# MCU.net
KiCad netlist of a schematic drawn in Altium Designer
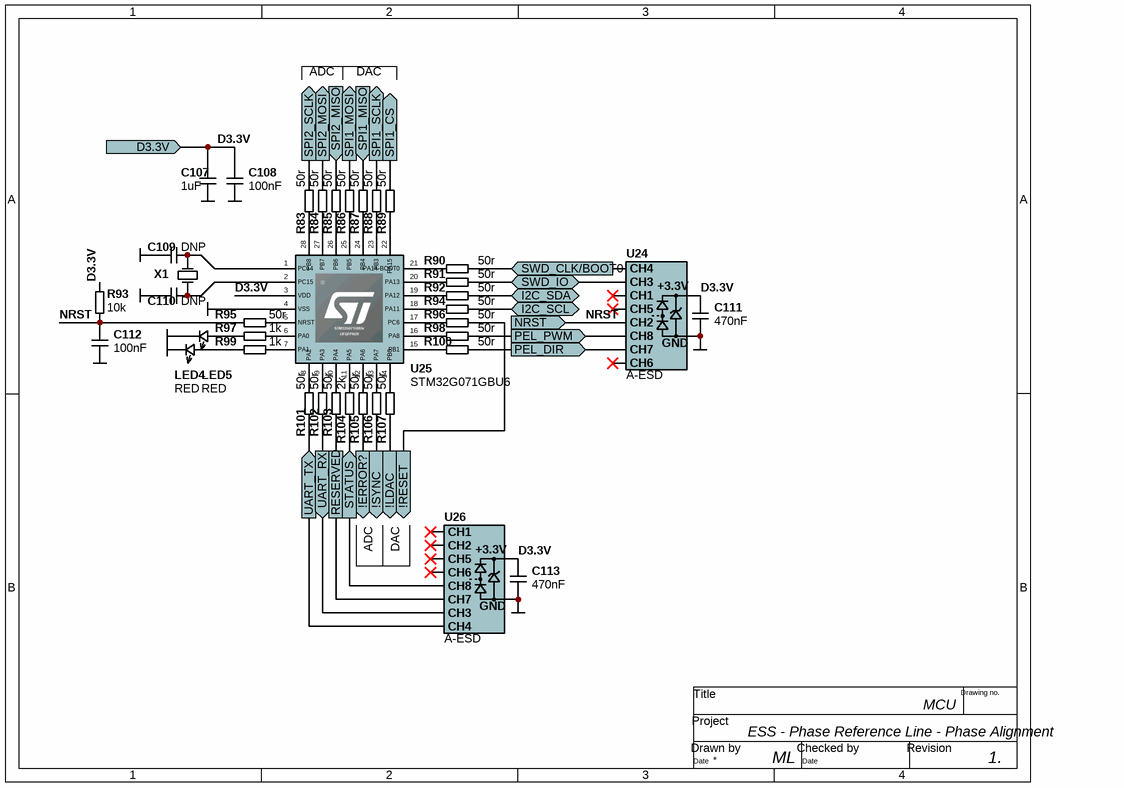
[diagram p0: MCU.SchDoc]

(export (version "E")
  (design (tool "Eeschema 10.0.6"))
  (components
    (comp (ref "C107")
      (value "1uF")
      (footprint "0805-Capacitor")
      (description "Capacitor 0805")
      (fields (field (name "TOLERANCE") "±20%"))
      (libsource (lib "PRL_PDC") (part "C_0805"))
    )
    (comp (ref "C108")
      (value "100nF")
      (footprint "0402-Capacitor")
      (description "Capacitor 0402")
      (fields (field (name "TOLERANCE") "±20%"))
      (libsource (lib "PRL_PDC") (part "C_0402"))
    )
    (comp (ref "C109")
      (value "DNP")
      (footprint "0402-Capacitor")
      (description "Capacitor 0402")
      (fields (field (name "TOLERANCE") "±20%"))
      (libsource (lib "PRL_PDC") (part "C_0402"))
    )
    (comp (ref "C110")
      (value "DNP")
      (footprint "0402-Capacitor")
      (description "Capacitor 0402")
      (fields (field (name "TOLERANCE") "±20%"))
      (libsource (lib "PRL_PDC") (part "C_0402"))
    )
    (comp (ref "C111")
      (value "470nF")
      (footprint "0402-Capacitor")
      (description "Capacitor 0402")
      (fields (field (name "TOLERANCE") "±20%"))
      (libsource (lib "PRL_PDC") (part "C_0402"))
    )
    (comp (ref "C112")
      (value "100nF")
      (footprint "0402-Capacitor")
      (description "Capacitor 0402")
      (fields (field (name "TOLERANCE") "±20%"))
      (libsource (lib "PRL_PDC") (part "C_0402"))
    )
    (comp (ref "C113")
      (value "470nF")
      (footprint "0402-Capacitor")
      (description "Capacitor 0402")
      (fields (field (name "TOLERANCE") "±20%"))
      (libsource (lib "PRL_PDC") (part "C_0402"))
    )
    (comp (ref "LED4") (value "RED") (footprint "LED0603") (libsource (lib "PRL_PDC") (part "LED0603")))
    (comp (ref "LED5") (value "RED") (footprint "LED0603") (libsource (lib "PRL_PDC") (part "LED0603")))
    (comp (ref "R83")
      (value "50r")
      (footprint "0402-RESISTOR")
      (description "Resistor 0402")
      (fields (field (name "TOLERANCE") "±1%"))
      (libsource (lib "PRL_PDC") (part "R_0402"))
    )
    (comp (ref "R84")
      (value "50r")
      (footprint "0402-RESISTOR")
      (description "Resistor 0402")
      (fields (field (name "TOLERANCE") "±1%"))
      (libsource (lib "PRL_PDC") (part "R_0402"))
    )
    (comp (ref "R85")
      (value "50r")
      (footprint "0402-RESISTOR")
      (description "Resistor 0402")
      (fields (field (name "TOLERANCE") "±1%"))
      (libsource (lib "PRL_PDC") (part "R_0402"))
    )
    (comp (ref "R86")
      (value "50r")
      (footprint "0402-RESISTOR")
      (description "Resistor 0402")
      (fields (field (name "TOLERANCE") "±1%"))
      (libsource (lib "PRL_PDC") (part "R_0402"))
    )
    (comp (ref "R87")
      (value "50r")
      (footprint "0402-RESISTOR")
      (description "Resistor 0402")
      (fields (field (name "TOLERANCE") "±1%"))
      (libsource (lib "PRL_PDC") (part "R_0402"))
    )
    (comp (ref "R88")
      (value "50r")
      (footprint "0402-RESISTOR")
      (description "Resistor 0402")
      (fields (field (name "TOLERANCE") "±1%"))
      (libsource (lib "PRL_PDC") (part "R_0402"))
    )
    (comp (ref "R89")
      (value "50r")
      (footprint "0402-RESISTOR")
      (description "Resistor 0402")
      (fields (field (name "TOLERANCE") "±1%"))
      (libsource (lib "PRL_PDC") (part "R_0402"))
    )
    (comp (ref "R90")
      (value "50r")
      (footprint "0402-RESISTOR")
      (description "Resistor 0402")
      (fields (field (name "TOLERANCE") "±1%"))
      (libsource (lib "") (part "R_0402_1"))
    )
    (comp (ref "R91")
      (value "50r")
      (footprint "0402-RESISTOR")
      (description "Resistor 0402")
      (fields (field (name "TOLERANCE") "±1%"))
      (libsource (lib "") (part "R_0402_1"))
    )
    (comp (ref "R92")
      (value "50r")
      (footprint "0402-RESISTOR")
      (description "Resistor 0402")
      (fields (field (name "TOLERANCE") "±1%"))
      (libsource (lib "") (part "R_0402_1"))
    )
    (comp (ref "R93")
      (value "10k")
      (footprint "0402-RESISTOR")
      (description "Resistor 0402")
      (fields (field (name "TOLERANCE") "±1%"))
      (libsource (lib "") (part "R_0402_2"))
    )
    (comp (ref "R94")
      (value "50r")
      (footprint "0402-RESISTOR")
      (description "Resistor 0402")
      (fields (field (name "TOLERANCE") "±1%"))
      (libsource (lib "") (part "R_0402_1"))
    )
    (comp (ref "R95")
      (value "50r")
      (footprint "0402-RESISTOR")
      (description "Resistor 0402")
      (fields (field (name "TOLERANCE") "±1%"))
      (libsource (lib "") (part "R_0402_1"))
    )
    (comp (ref "R96")
      (value "50r")
      (footprint "0402-RESISTOR")
      (description "Resistor 0402")
      (fields (field (name "TOLERANCE") "±1%"))
      (libsource (lib "") (part "R_0402_1"))
    )
    (comp (ref "R97")
      (value "1k")
      (footprint "0402-RESISTOR")
      (description "Resistor 0402")
      (fields (field (name "TOLERANCE") "±1%"))
      (libsource (lib "") (part "R_0402_3"))
    )
    (comp (ref "R98")
      (value "50r")
      (footprint "0402-RESISTOR")
      (description "Resistor 0402")
      (fields (field (name "TOLERANCE") "±1%"))
      (libsource (lib "") (part "R_0402_1"))
    )
    (comp (ref "R99")
      (value "1k")
      (footprint "0402-RESISTOR")
      (description "Resistor 0402")
      (fields (field (name "TOLERANCE") "±1%"))
      (libsource (lib "") (part "R_0402_3"))
    )
    (comp (ref "R100")
      (value "50r")
      (footprint "0402-RESISTOR")
      (description "Resistor 0402")
      (fields (field (name "TOLERANCE") "±1%"))
      (libsource (lib "") (part "R_0402_1"))
    )
    (comp (ref "R101")
      (value "50r")
      (footprint "0402-RESISTOR")
      (description "Resistor 0402")
      (fields (field (name "TOLERANCE") "±1%"))
      (libsource (lib "") (part "R_0402_2"))
    )
    (comp (ref "R102")
      (value "50r")
      (footprint "0402-RESISTOR")
      (description "Resistor 0402")
      (fields (field (name "TOLERANCE") "±1%"))
      (libsource (lib "") (part "R_0402_2"))
    )
    (comp (ref "R103")
      (value "50r")
      (footprint "0402-RESISTOR")
      (description "Resistor 0402")
      (fields (field (name "TOLERANCE") "±1%"))
      (libsource (lib "") (part "R_0402_2"))
    )
    (comp (ref "R104")
      (value "2k")
      (footprint "0402-RESISTOR")
      (description "Resistor 0402")
      (fields (field (name "TOLERANCE") "±1%"))
      (libsource (lib "") (part "R_0402_2"))
    )
    (comp (ref "R105")
      (value "50r")
      (footprint "0402-RESISTOR")
      (description "Resistor 0402")
      (fields (field (name "TOLERANCE") "±1%"))
      (libsource (lib "") (part "R_0402_2"))
    )
    (comp (ref "R106")
      (value "50r")
      (footprint "0402-RESISTOR")
      (description "Resistor 0402")
      (fields (field (name "TOLERANCE") "±1%"))
      (libsource (lib "") (part "R_0402_2"))
    )
    (comp (ref "R107")
      (value "50r")
      (footprint "0402-RESISTOR")
      (description "Resistor 0402")
      (fields (field (name "TOLERANCE") "±1%"))
      (libsource (lib "") (part "R_0402_2"))
    )
    (comp (ref "U24")
      (value "A-ESD")
      (footprint "MSOP10 3x3mm")
      (description "8-Channel\r\nLow Capacitance ESD\r\nProtection Array")
      (libsource (lib "PRL_PDC") (part "CM1213-08MR"))
    )
    (comp (ref "U25")
      (value "STM32G071GBU6")
      (footprint "UFQFPN-28")
      (description "IC MCU 32BIT 128KB FLASH 28QFPN")
      (libsource (lib "PRL_PDC") (part "STM32G071GBU6"))
    )
    (comp (ref "U26")
      (value "A-ESD")
      (footprint "MSOP10 3x3mm")
      (description "8-Channel\r\nLow Capacitance ESD\r\nProtection Array")
      (libsource (lib "") (part "CM1213-08MR_1"))
    )
    (comp (ref "X1")
      (value "32.768KHz")
      (footprint "2-SMD-XTAL")
      (description "32.768kHz ±20ppm Crystal 6pF 55 kOhms 2-SMD, No Lead")
      (libsource (lib "PRL_PDC") (part "XTAL_ABS07-120-32.768KHZ-T"))
    )
  )
  (nets
    (net (code "1") (name "/!ERROR?") (class "Default")
      (node (ref "R105") (pin "1") (pinfunction "1_1") (pintype "passive"))
    )
    (net (code "2") (name "/!LDAC") (class "Default")
      (node (ref "R107") (pin "1") (pinfunction "1_1") (pintype "passive"))
    )
    (net (code "3") (name "/!RESET") (class "Default")
      (node (ref "R96") (pin "1") (pinfunction "1_1") (pintype "passive"))
    )
    (net (code "4") (name "/!SYNC") (class "Default")
      (node (ref "R106") (pin "1") (pinfunction "1_1") (pintype "passive"))
    )
    (net (code "5") (name "/D3.3V") (class "Default")
      (node (ref "C107") (pin "1") (pinfunction "1_1") (pintype "passive"))
      (node (ref "C108") (pin "1") (pinfunction "1_1") (pintype "passive"))
      (node (ref "C111") (pin "1") (pinfunction "1_1") (pintype "passive"))
      (node (ref "C113") (pin "1") (pinfunction "1_1") (pintype "passive"))
      (node (ref "R93") (pin "2") (pinfunction "2_2") (pintype "passive"))
      (node (ref "U24") (pin "8") (pinfunction "VP_8") (pintype "passive"))
      (node (ref "U25") (pin "3") (pinfunction "VDD_3") (pintype "passive"))
      (node (ref "U26") (pin "8") (pinfunction "VP_8") (pintype "passive"))
    )
    (net (code "6") (name "/I2C_SCL") (class "Default")
      (node (ref "R94") (pin "1") (pinfunction "1_1") (pintype "passive"))
    )
    (net (code "7") (name "/I2C_SDA") (class "Default")
      (node (ref "R92") (pin "1") (pinfunction "1_1") (pintype "passive"))
    )
    (net (code "8") (name "/NRST") (class "Default")
      (node (ref "C112") (pin "1") (pinfunction "1_1") (pintype "passive"))
      (node (ref "R93") (pin "1") (pinfunction "1_1") (pintype "passive"))
      (node (ref "R95") (pin "2") (pinfunction "2_2") (pintype "passive"))
      (node (ref "U24") (pin "2") (pinfunction "CH2_2") (pintype "passive"))
    )
    (net (code "9") (name "/PEL_DIR") (class "Default")
      (node (ref "R100") (pin "1") (pinfunction "1_1") (pintype "passive"))
      (node (ref "U24") (pin "9") (pinfunction "CH7_9") (pintype "passive"))
    )
    (net (code "10") (name "/PEL_PWM") (class "Default")
      (node (ref "R98") (pin "1") (pinfunction "1_1") (pintype "passive"))
      (node (ref "U24") (pin "10") (pinfunction "CH8_10") (pintype "passive"))
    )
    (net (code "11") (name "/RESERVED") (class "Default")
      (node (ref "R103") (pin "1") (pinfunction "1_1") (pintype "passive"))
      (node (ref "U26") (pin "9") (pinfunction "CH7_9") (pintype "passive"))
    )
    (net (code "12") (name "/SPI1_CS") (class "Default")
      (node (ref "R89") (pin "1") (pinfunction "1_1") (pintype "passive"))
    )
    (net (code "13") (name "/SPI1_MISO") (class "Default")
      (node (ref "R87") (pin "1") (pinfunction "1_1") (pintype "passive"))
    )
    (net (code "14") (name "/SPI1_MOSI") (class "Default")
      (node (ref "R86") (pin "1") (pinfunction "1_1") (pintype "passive"))
    )
    (net (code "15") (name "/SPI1_SCLK") (class "Default")
      (node (ref "R88") (pin "1") (pinfunction "1_1") (pintype "passive"))
    )
    (net (code "16") (name "/SPI2_MISO") (class "Default")
      (node (ref "R85") (pin "1") (pinfunction "1_1") (pintype "passive"))
    )
    (net (code "17") (name "/SPI2_MOSI") (class "Default")
      (node (ref "R84") (pin "1") (pinfunction "1_1") (pintype "passive"))
    )
    (net (code "18") (name "/SPI2_SCLK") (class "Default")
      (node (ref "R83") (pin "1") (pinfunction "1_1") (pintype "passive"))
    )
    (net (code "19") (name "/STATUS") (class "Default")
      (node (ref "R104") (pin "1") (pinfunction "1_1") (pintype "passive"))
      (node (ref "U26") (pin "10") (pinfunction "CH8_10") (pintype "passive"))
    )
    (net (code "20") (name "/SWD_CLK{slash}BOOT0") (class "Default")
      (node (ref "R90") (pin "1") (pinfunction "1_1") (pintype "passive"))
      (node (ref "U24") (pin "4") (pinfunction "CH4_4") (pintype "passive"))
    )
    (net (code "21") (name "/SWD_IO") (class "Default")
      (node (ref "R91") (pin "1") (pinfunction "1_1") (pintype "passive"))
      (node (ref "U24") (pin "3") (pinfunction "CH3_3") (pintype "passive"))
    )
    (net (code "22") (name "/UART_RX") (class "Default")
      (node (ref "R102") (pin "1") (pinfunction "1_1") (pintype "passive"))
      (node (ref "U26") (pin "3") (pinfunction "CH3_3") (pintype "passive"))
    )
    (net (code "23") (name "/UART_TX") (class "Default")
      (node (ref "R101") (pin "1") (pinfunction "1_1") (pintype "passive"))
      (node (ref "U26") (pin "4") (pinfunction "CH4_4") (pintype "passive"))
    )
    (net (code "24") (name "DGND") (class "Default")
      (node (ref "C107") (pin "2") (pinfunction "2_2") (pintype "passive"))
      (node (ref "C108") (pin "2") (pinfunction "2_2") (pintype "passive"))
      (node (ref "C109") (pin "1") (pinfunction "1_1") (pintype "passive"))
      (node (ref "C110") (pin "1") (pinfunction "1_1") (pintype "passive"))
      (node (ref "C111") (pin "2") (pinfunction "2_2") (pintype "passive"))
      (node (ref "C112") (pin "2") (pinfunction "2_2") (pintype "passive"))
      (node (ref "C113") (pin "2") (pinfunction "2_2") (pintype "passive"))
      (node (ref "LED4") (pin "K") (pinfunction "K_K") (pintype "passive"))
      (node (ref "LED5") (pin "K") (pinfunction "K_K") (pintype "passive"))
      (node (ref "U24") (pin "5") (pinfunction "VN_5") (pintype "passive"))
      (node (ref "U25") (pin "4") (pinfunction "VSS_4") (pintype "passive"))
      (node (ref "U26") (pin "5") (pinfunction "VN_5") (pintype "passive"))
    )
    (net (code "25") (name "Net-(LED4-PadA)") (class "Default")
      (node (ref "LED4") (pin "A") (pinfunction "A_A") (pintype "passive"))
      (node (ref "R99") (pin "1") (pinfunction "1_1") (pintype "passive"))
    )
    (net (code "26") (name "Net-(LED5-PadA)") (class "Default")
      (node (ref "LED5") (pin "A") (pinfunction "A_A") (pintype "passive"))
      (node (ref "R97") (pin "1") (pinfunction "1_1") (pintype "passive"))
    )
    (net (code "27") (name "Net-(U25-NRST)") (class "Default")
      (node (ref "R95") (pin "1") (pinfunction "1_1") (pintype "passive"))
      (node (ref "U25") (pin "5") (pinfunction "NRST_5") (pintype "passive"))
    )
    (net (code "28") (name "Net-(U25-PA0)") (class "Default")
      (node (ref "R97") (pin "2") (pinfunction "2_2") (pintype "passive"))
      (node (ref "U25") (pin "6") (pinfunction "PA0_6") (pintype "passive"))
    )
    (net (code "29") (name "Net-(U25-PA1)") (class "Default")
      (node (ref "R99") (pin "2") (pinfunction "2_2") (pintype "passive"))
      (node (ref "U25") (pin "7") (pinfunction "PA1_7") (pintype "passive"))
    )
    (net (code "30") (name "Net-(U25-PA2)") (class "Default")
      (node (ref "R101") (pin "2") (pinfunction "2_2") (pintype "passive"))
      (node (ref "U25") (pin "8") (pinfunction "PA2_8") (pintype "passive"))
    )
    (net (code "31") (name "Net-(U25-PA3)") (class "Default")
      (node (ref "R102") (pin "2") (pinfunction "2_2") (pintype "passive"))
      (node (ref "U25") (pin "9") (pinfunction "PA3_9") (pintype "passive"))
    )
    (net (code "32") (name "Net-(U25-PA4)") (class "Default")
      (node (ref "R103") (pin "2") (pinfunction "2_2") (pintype "passive"))
      (node (ref "U25") (pin "10") (pinfunction "PA4_10") (pintype "passive"))
    )
    (net (code "33") (name "Net-(U25-PA5)") (class "Default")
      (node (ref "R104") (pin "2") (pinfunction "2_2") (pintype "passive"))
      (node (ref "U25") (pin "11") (pinfunction "PA5_11") (pintype "passive"))
    )
    (net (code "34") (name "Net-(U25-PA6)") (class "Default")
      (node (ref "R105") (pin "2") (pinfunction "2_2") (pintype "passive"))
      (node (ref "U25") (pin "12") (pinfunction "PA6_12") (pintype "passive"))
    )
    (net (code "35") (name "Net-(U25-PA7)") (class "Default")
      (node (ref "R106") (pin "2") (pinfunction "2_2") (pintype "passive"))
      (node (ref "U25") (pin "13") (pinfunction "PA7_13") (pintype "passive"))
    )
    (net (code "36") (name "Net-(U25-PA8)") (class "Default")
      (node (ref "R98") (pin "2") (pinfunction "2_2") (pintype "passive"))
      (node (ref "U25") (pin "16") (pinfunction "PA8_16") (pintype "passive"))
    )
    (net (code "37") (name "Net-(U25-PA11)") (class "Default")
      (node (ref "R94") (pin "2") (pinfunction "2_2") (pintype "passive"))
      (node (ref "U25") (pin "18") (pinfunction "PA11_18") (pintype "passive"))
    )
    (net (code "38") (name "Net-(U25-PA12)") (class "Default")
      (node (ref "R92") (pin "2") (pinfunction "2_2") (pintype "passive"))
      (node (ref "U25") (pin "19") (pinfunction "PA12_19") (pintype "passive"))
    )
    (net (code "39") (name "Net-(U25-PA13)") (class "Default")
      (node (ref "R91") (pin "2") (pinfunction "2_2") (pintype "passive"))
      (node (ref "U25") (pin "20") (pinfunction "PA13_20") (pintype "passive"))
    )
    (net (code "40") (name "Net-(U25-PA14-BOOT0)") (class "Default")
      (node (ref "R90") (pin "2") (pinfunction "2_2") (pintype "passive"))
      (node (ref "U25") (pin "21") (pinfunction "PA14-BOOT0_21") (pintype "passive"))
    )
    (net (code "41") (name "Net-(U25-PA15)") (class "Default")
      (node (ref "R89") (pin "2") (pinfunction "2_2") (pintype "passive"))
      (node (ref "U25") (pin "22") (pinfunction "PA15_22") (pintype "passive"))
    )
    (net (code "42") (name "Net-(U25-PB0)") (class "Default")
      (node (ref "R107") (pin "2") (pinfunction "2_2") (pintype "passive"))
      (node (ref "U25") (pin "14") (pinfunction "PB0_14") (pintype "passive"))
    )
    (net (code "43") (name "Net-(U25-PB1)") (class "Default")
      (node (ref "R100") (pin "2") (pinfunction "2_2") (pintype "passive"))
      (node (ref "U25") (pin "15") (pinfunction "PB1_15") (pintype "passive"))
    )
    (net (code "44") (name "Net-(U25-PB3)") (class "Default")
      (node (ref "R88") (pin "2") (pinfunction "2_2") (pintype "passive"))
      (node (ref "U25") (pin "23") (pinfunction "PB3_23") (pintype "passive"))
    )
    (net (code "45") (name "Net-(U25-PB4)") (class "Default")
      (node (ref "R87") (pin "2") (pinfunction "2_2") (pintype "passive"))
      (node (ref "U25") (pin "24") (pinfunction "PB4_24") (pintype "passive"))
    )
    (net (code "46") (name "Net-(U25-PB5)") (class "Default")
      (node (ref "R86") (pin "2") (pinfunction "2_2") (pintype "passive"))
      (node (ref "U25") (pin "25") (pinfunction "PB5_25") (pintype "passive"))
    )
    (net (code "47") (name "Net-(U25-PB6)") (class "Default")
      (node (ref "R85") (pin "2") (pinfunction "2_2") (pintype "passive"))
      (node (ref "U25") (pin "26") (pinfunction "PB6_26") (pintype "passive"))
    )
    (net (code "48") (name "Net-(U25-PB7)") (class "Default")
      (node (ref "R84") (pin "2") (pinfunction "2_2") (pintype "passive"))
      (node (ref "U25") (pin "27") (pinfunction "PB7_27") (pintype "passive"))
    )
    (net (code "49") (name "Net-(U25-PB8)") (class "Default")
      (node (ref "R83") (pin "2") (pinfunction "2_2") (pintype "passive"))
      (node (ref "U25") (pin "28") (pinfunction "PB8_28") (pintype "passive"))
    )
    (net (code "50") (name "Net-(U25-PC6)") (class "Default")
      (node (ref "R96") (pin "2") (pinfunction "2_2") (pintype "passive"))
      (node (ref "U25") (pin "17") (pinfunction "PC6_17") (pintype "passive"))
    )
    (net (code "51") (name "Net-(U25-PC14)") (class "Default")
      (node (ref "C109") (pin "2") (pinfunction "2_2") (pintype "passive"))
      (node (ref "U25") (pin "1") (pinfunction "PC14_1") (pintype "passive"))
      (node (ref "X1") (pin "2") (pinfunction "OSC2_2") (pintype "passive"))
    )
    (net (code "52") (name "Net-(U25-PC15)") (class "Default")
      (node (ref "C110") (pin "2") (pinfunction "2_2") (pintype "passive"))
      (node (ref "U25") (pin "2") (pinfunction "PC15_2") (pintype "passive"))
      (node (ref "X1") (pin "1") (pinfunction "OSC1_1") (pintype "passive"))
    )
    (net (code "53") (name "unconnected-(U24-CH1-Pad1)") (class "Default")
      (node (ref "U24") (pin "1") (pinfunction "CH1_1") (pintype "passive+no_connect"))
    )
    (net (code "54") (name "unconnected-(U24-CH5-Pad6)") (class "Default")
      (node (ref "U24") (pin "6") (pinfunction "CH5_6") (pintype "passive+no_connect"))
    )
    (net (code "55") (name "unconnected-(U24-CH6-Pad7)") (class "Default")
      (node (ref "U24") (pin "7") (pinfunction "CH6_7") (pintype "passive+no_connect"))
    )
    (net (code "56") (name "unconnected-(U26-CH1-Pad1)") (class "Default")
      (node (ref "U26") (pin "1") (pinfunction "CH1_1") (pintype "passive+no_connect"))
    )
    (net (code "57") (name "unconnected-(U26-CH2-Pad2)") (class "Default")
      (node (ref "U26") (pin "2") (pinfunction "CH2_2") (pintype "passive+no_connect"))
    )
    (net (code "58") (name "unconnected-(U26-CH5-Pad6)") (class "Default")
      (node (ref "U26") (pin "6") (pinfunction "CH5_6") (pintype "passive+no_connect"))
    )
    (net (code "59") (name "unconnected-(U26-CH6-Pad7)") (class "Default")
      (node (ref "U26") (pin "7") (pinfunction "CH6_7") (pintype "passive+no_connect"))
    )
  )
)
